# SDC_project.net
KiCad netlist of a schematic drawn in EAGLE
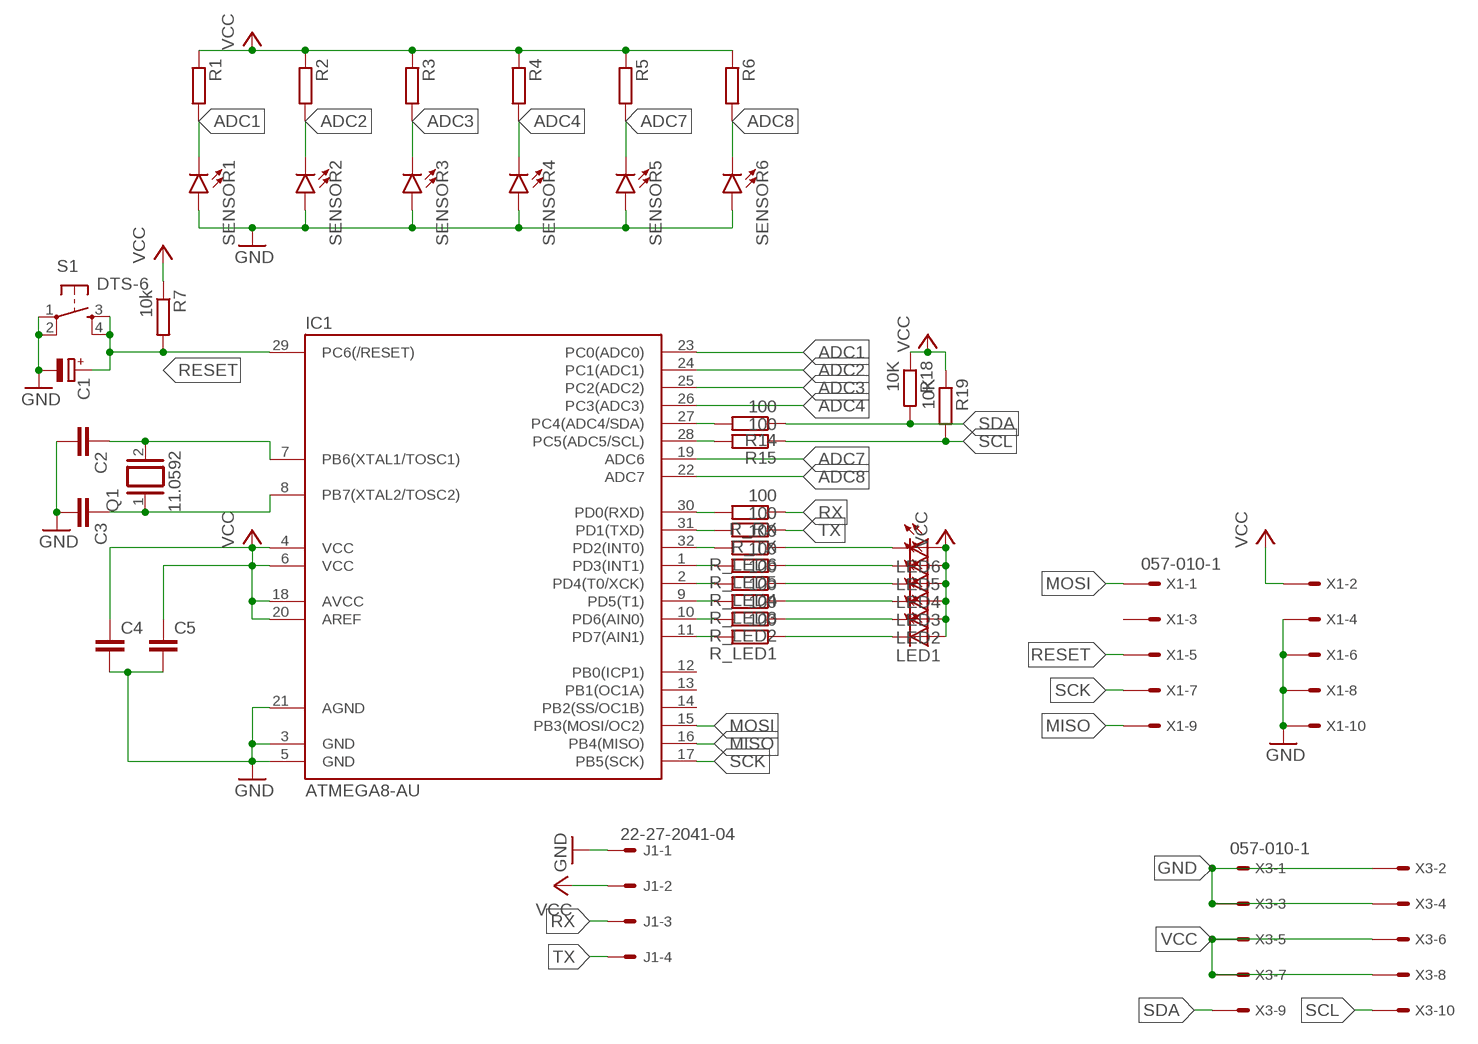
[diagram p0: schematic, sheet 1]

(export (version "E")
  (design (tool "Eeschema 10.0.6"))
  (components
    (comp (ref "C1")
      (value "CPOL-EUE2.5-5")
      (footprint "eagle-import:E2,5-5")
      (libsource (lib "eagle-import") (part "CPOL-EUE2.5-5"))
    )
    (comp (ref "C2")
      (value "C5/2.5")
      (footprint "eagle-import:C5B2.5")
      (libsource (lib "eagle-import") (part "C5/2.5"))
    )
    (comp (ref "C3")
      (value "C5/2.5")
      (footprint "eagle-import:C5B2.5")
      (libsource (lib "eagle-import") (part "C5/2.5"))
    )
    (comp (ref "C4")
      (value "C-EUC1206")
      (footprint "eagle-import:C1206")
      (libsource (lib "eagle-import") (part "C-EUC1206"))
    )
    (comp (ref "C5")
      (value "C-EUC1206")
      (footprint "eagle-import:C1206")
      (libsource (lib "eagle-import") (part "C-EUC1206"))
    )
    (comp (ref "IC1")
      (value "ATMEGA8-AU")
      (footprint "eagle-import:TQFP32-08")
      (libsource (lib "eagle-import") (part "ATMEGA8-AU"))
    )
    (comp (ref "J1")
      (value "22-27-2041-04")
      (footprint "eagle-import:6410-04")
      (fields (field (name "MF") "MOLEX"))
      (libsource (lib "eagle-import") (part "22-?-0427-2041"))
    )
    (comp (ref "LED1")
      (value "LEDSML0805")
      (footprint "eagle-import:SML0805")
      (libsource (lib "eagle-import") (part "LEDSML0805"))
    )
    (comp (ref "LED2")
      (value "LEDSML0805")
      (footprint "eagle-import:SML0805")
      (libsource (lib "eagle-import") (part "LEDSML0805"))
    )
    (comp (ref "LED3")
      (value "LEDSML0805")
      (footprint "eagle-import:SML0805")
      (libsource (lib "eagle-import") (part "LEDSML0805"))
    )
    (comp (ref "LED4")
      (value "LEDSML0805")
      (footprint "eagle-import:SML0805")
      (libsource (lib "eagle-import") (part "LEDSML0805"))
    )
    (comp (ref "LED5")
      (value "LEDSML0805")
      (footprint "eagle-import:SML0805")
      (libsource (lib "eagle-import") (part "LEDSML0805"))
    )
    (comp (ref "LED6")
      (value "LEDSML0805")
      (footprint "eagle-import:SML0805")
      (libsource (lib "eagle-import") (part "LEDSML0805"))
    )
    (comp (ref "Q1")
      (value "11.0592")
      (footprint "eagle-import:QS")
      (libsource (lib "eagle-import") (part "XTAL/S"))
    )
    (comp (ref "R1")
      (value "R-EU_R0805")
      (footprint "eagle-import:R0805")
      (libsource (lib "eagle-import") (part "R-EU_R0805"))
    )
    (comp (ref "R2")
      (value "R-EU_R0805")
      (footprint "eagle-import:R0805")
      (libsource (lib "eagle-import") (part "R-EU_R0805"))
    )
    (comp (ref "R3")
      (value "R-EU_R0805")
      (footprint "eagle-import:R0805")
      (libsource (lib "eagle-import") (part "R-EU_R0805"))
    )
    (comp (ref "R4")
      (value "R-EU_R0805")
      (footprint "eagle-import:R0805")
      (libsource (lib "eagle-import") (part "R-EU_R0805"))
    )
    (comp (ref "R5")
      (value "R-EU_R0805")
      (footprint "eagle-import:R0805")
      (libsource (lib "eagle-import") (part "R-EU_R0805"))
    )
    (comp (ref "R6")
      (value "R-EU_R0805")
      (footprint "eagle-import:R0805")
      (libsource (lib "eagle-import") (part "R-EU_R0805"))
    )
    (comp (ref "R7")
      (value "10k")
      (footprint "eagle-import:R0805")
      (libsource (lib "eagle-import") (part "R-EU_R0805"))
    )
    (comp (ref "R14")
      (value "100")
      (footprint "eagle-import:R0805")
      (libsource (lib "eagle-import") (part "R-EU_R0805"))
    )
    (comp (ref "R15")
      (value "100")
      (footprint "eagle-import:R0805")
      (libsource (lib "eagle-import") (part "R-EU_R0805"))
    )
    (comp (ref "R18")
      (value "10K")
      (footprint "eagle-import:R0805")
      (libsource (lib "eagle-import") (part "R-EU_R0805"))
    )
    (comp (ref "R19")
      (value "10K")
      (footprint "eagle-import:R0805")
      (libsource (lib "eagle-import") (part "R-EU_R0805"))
    )
    (comp (ref "R_LED1")
      (value "100")
      (footprint "eagle-import:R0805")
      (libsource (lib "eagle-import") (part "R-EU_R0805"))
    )
    (comp (ref "R_LED2")
      (value "100")
      (footprint "eagle-import:R0805")
      (libsource (lib "eagle-import") (part "R-EU_R0805"))
    )
    (comp (ref "R_LED3")
      (value "100")
      (footprint "eagle-import:R0805")
      (libsource (lib "eagle-import") (part "R-EU_R0805"))
    )
    (comp (ref "R_LED4")
      (value "100")
      (footprint "eagle-import:R0805")
      (libsource (lib "eagle-import") (part "R-EU_R0805"))
    )
    (comp (ref "R_LED5")
      (value "100")
      (footprint "eagle-import:R0805")
      (libsource (lib "eagle-import") (part "R-EU_R0805"))
    )
    (comp (ref "R_LED6")
      (value "100")
      (footprint "eagle-import:R0805")
      (libsource (lib "eagle-import") (part "R-EU_R0805"))
    )
    (comp (ref "R_RX")
      (value "100")
      (footprint "eagle-import:R0805")
      (libsource (lib "eagle-import") (part "R-EU_R0805"))
    )
    (comp (ref "R_TX")
      (value "100")
      (footprint "eagle-import:R0805")
      (libsource (lib "eagle-import") (part "R-EU_R0805"))
    )
    (comp (ref "S1")
      (value "DTS-6")
      (footprint "eagle-import:DTS-6")
      (libsource (lib "eagle-import") (part "DTS-6"))
    )
    (comp (ref "SENSOR1")
      (value "LED5MM")
      (footprint "eagle-import:LED_5MM")
      (libsource (lib "eagle-import") (part "LED5MM"))
    )
    (comp (ref "SENSOR2")
      (value "LED5MM")
      (footprint "eagle-import:LED_5MM")
      (libsource (lib "eagle-import") (part "LED5MM"))
    )
    (comp (ref "SENSOR3")
      (value "LED5MM")
      (footprint "eagle-import:LED_5MM")
      (libsource (lib "eagle-import") (part "LED5MM"))
    )
    (comp (ref "SENSOR4")
      (value "LED5MM")
      (footprint "eagle-import:LED_5MM")
      (libsource (lib "eagle-import") (part "LED5MM"))
    )
    (comp (ref "SENSOR5")
      (value "LED5MM")
      (footprint "eagle-import:LED_5MM")
      (libsource (lib "eagle-import") (part "LED5MM"))
    )
    (comp (ref "SENSOR6")
      (value "LED5MM")
      (footprint "eagle-import:LED_5MM")
      (libsource (lib "eagle-import") (part "LED5MM"))
    )
    (comp (ref "X1")
      (value "057-010-1")
      (footprint "eagle-import:057-010-1")
      (libsource (lib "eagle-import") (part "057-010-1"))
    )
    (comp (ref "X3")
      (value "057-010-1")
      (footprint "eagle-import:057-010-1")
      (libsource (lib "eagle-import") (part "057-010-1"))
    )
  )
  (nets
    (net (code "1") (name "ADC1") (class "Default")
      (node (ref "IC1") (pin "23") (pinfunction "PC0(ADC0)_23") (pintype "bidirectional"))
      (node (ref "R1") (pin "2") (pinfunction "2_2") (pintype "passive"))
      (node (ref "SENSOR1") (pin "K") (pinfunction "C_K") (pintype "passive"))
    )
    (net (code "2") (name "ADC2") (class "Default")
      (node (ref "IC1") (pin "24") (pinfunction "PC1(ADC1)_24") (pintype "bidirectional"))
      (node (ref "R2") (pin "2") (pinfunction "2_2") (pintype "passive"))
      (node (ref "SENSOR2") (pin "K") (pinfunction "C_K") (pintype "passive"))
    )
    (net (code "3") (name "ADC3") (class "Default")
      (node (ref "IC1") (pin "25") (pinfunction "PC2(ADC2)_25") (pintype "bidirectional"))
      (node (ref "R3") (pin "2") (pinfunction "2_2") (pintype "passive"))
      (node (ref "SENSOR3") (pin "K") (pinfunction "C_K") (pintype "passive"))
    )
    (net (code "4") (name "ADC4") (class "Default")
      (node (ref "IC1") (pin "26") (pinfunction "PC3(ADC3)_26") (pintype "bidirectional"))
      (node (ref "R4") (pin "2") (pinfunction "2_2") (pintype "passive"))
      (node (ref "SENSOR4") (pin "K") (pinfunction "C_K") (pintype "passive"))
    )
    (net (code "5") (name "ADC7") (class "Default")
      (node (ref "IC1") (pin "19") (pinfunction "ADC6_19") (pintype "passive"))
      (node (ref "R5") (pin "2") (pinfunction "2_2") (pintype "passive"))
      (node (ref "SENSOR5") (pin "K") (pinfunction "C_K") (pintype "passive"))
    )
    (net (code "6") (name "ADC8") (class "Default")
      (node (ref "IC1") (pin "22") (pinfunction "ADC7_22") (pintype "passive"))
      (node (ref "R6") (pin "2") (pinfunction "2_2") (pintype "passive"))
      (node (ref "SENSOR6") (pin "K") (pinfunction "C_K") (pintype "passive"))
    )
    (net (code "7") (name "GND") (class "Default")
      (node (ref "C1") (pin "-") (pinfunction "-_-") (pintype "passive"))
      (node (ref "C2") (pin "2") (pinfunction "2_2") (pintype "passive"))
      (node (ref "C3") (pin "2") (pinfunction "2_2") (pintype "passive"))
      (node (ref "C4") (pin "2") (pinfunction "2_2") (pintype "passive"))
      (node (ref "C5") (pin "2") (pinfunction "2_2") (pintype "passive"))
      (node (ref "IC1") (pin "21") (pinfunction "AGND_21") (pintype "power_in"))
      (node (ref "IC1") (pin "3") (pinfunction "GND_3") (pintype "power_in"))
      (node (ref "IC1") (pin "5") (pinfunction "GND_5") (pintype "power_in"))
      (node (ref "J1") (pin "1") (pinfunction "S_1") (pintype "passive"))
      (node (ref "S1") (pin "1") (pinfunction "1_1") (pintype "passive"))
      (node (ref "S1") (pin "2") (pinfunction "2_2") (pintype "passive"))
      (node (ref "SENSOR1") (pin "A") (pinfunction "A_A") (pintype "passive"))
      (node (ref "SENSOR2") (pin "A") (pinfunction "A_A") (pintype "passive"))
      (node (ref "SENSOR3") (pin "A") (pinfunction "A_A") (pintype "passive"))
      (node (ref "SENSOR4") (pin "A") (pinfunction "A_A") (pintype "passive"))
      (node (ref "SENSOR5") (pin "A") (pinfunction "A_A") (pintype "passive"))
      (node (ref "SENSOR6") (pin "A") (pinfunction "A_A") (pintype "passive"))
      (node (ref "X1") (pin "10") (pinfunction "S_10") (pintype "passive"))
      (node (ref "X1") (pin "4") (pinfunction "S_4") (pintype "passive"))
      (node (ref "X1") (pin "6") (pinfunction "S_6") (pintype "passive"))
      (node (ref "X1") (pin "8") (pinfunction "S_8") (pintype "passive"))
      (node (ref "X3") (pin "1") (pinfunction "S_1") (pintype "passive"))
      (node (ref "X3") (pin "2") (pinfunction "S_2") (pintype "passive"))
      (node (ref "X3") (pin "3") (pinfunction "S_3") (pintype "passive"))
      (node (ref "X3") (pin "4") (pinfunction "S_4") (pintype "passive"))
    )
    (net (code "8") (name "MISO") (class "Default")
      (node (ref "IC1") (pin "16") (pinfunction "PB4(MISO)_16") (pintype "bidirectional"))
      (node (ref "X1") (pin "9") (pinfunction "S_9") (pintype "passive"))
    )
    (net (code "9") (name "MOSI") (class "Default")
      (node (ref "IC1") (pin "15") (pinfunction "PB3(MOSI/OC2)_15") (pintype "bidirectional"))
      (node (ref "X1") (pin "1") (pinfunction "S_1") (pintype "passive"))
    )
    (net (code "10") (name "Net-(IC1-PB6(XTAL1{slash}TOSC1))") (class "Default")
      (node (ref "C2") (pin "1") (pinfunction "1_1") (pintype "passive"))
      (node (ref "IC1") (pin "7") (pinfunction "PB6(XTAL1/TOSC1)_7") (pintype "bidirectional"))
      (node (ref "Q1") (pin "2") (pinfunction "2_2") (pintype "passive"))
    )
    (net (code "11") (name "Net-(IC1-PB7(XTAL2{slash}TOSC2))") (class "Default")
      (node (ref "C3") (pin "1") (pinfunction "1_1") (pintype "passive"))
      (node (ref "IC1") (pin "8") (pinfunction "PB7(XTAL2/TOSC2)_8") (pintype "bidirectional"))
      (node (ref "Q1") (pin "1") (pinfunction "1_1") (pintype "passive"))
    )
    (net (code "12") (name "Net-(IC1-PC4(ADC4{slash}SDA))") (class "Default")
      (node (ref "IC1") (pin "27") (pinfunction "PC4(ADC4/SDA)_27") (pintype "bidirectional"))
      (node (ref "R14") (pin "2") (pinfunction "2_2") (pintype "passive"))
    )
    (net (code "13") (name "Net-(IC1-PC5(ADC5{slash}SCL))") (class "Default")
      (node (ref "IC1") (pin "28") (pinfunction "PC5(ADC5/SCL)_28") (pintype "bidirectional"))
      (node (ref "R15") (pin "2") (pinfunction "2_2") (pintype "passive"))
    )
    (net (code "14") (name "Net-(IC1-PD0(RXD))") (class "Default")
      (node (ref "IC1") (pin "30") (pinfunction "PD0(RXD)_30") (pintype "bidirectional"))
      (node (ref "R_RX") (pin "2") (pinfunction "2_2") (pintype "passive"))
    )
    (net (code "15") (name "Net-(IC1-PD1(TXD))") (class "Default")
      (node (ref "IC1") (pin "31") (pinfunction "PD1(TXD)_31") (pintype "bidirectional"))
      (node (ref "R_TX") (pin "2") (pinfunction "2_2") (pintype "passive"))
    )
    (net (code "16") (name "Net-(IC1-PD2(INT0))") (class "Default")
      (node (ref "IC1") (pin "32") (pinfunction "PD2(INT0)_32") (pintype "bidirectional"))
      (node (ref "R_LED6") (pin "2") (pinfunction "2_2") (pintype "passive"))
    )
    (net (code "17") (name "Net-(IC1-PD3(INT1))") (class "Default")
      (node (ref "IC1") (pin "1") (pinfunction "PD3(INT1)_1") (pintype "bidirectional"))
      (node (ref "R_LED5") (pin "2") (pinfunction "2_2") (pintype "passive"))
    )
    (net (code "18") (name "Net-(IC1-PD4(T0{slash}XCK))") (class "Default")
      (node (ref "IC1") (pin "2") (pinfunction "PD4(T0/XCK)_2") (pintype "bidirectional"))
      (node (ref "R_LED4") (pin "2") (pinfunction "2_2") (pintype "passive"))
    )
    (net (code "19") (name "Net-(IC1-PD5(T1))") (class "Default")
      (node (ref "IC1") (pin "9") (pinfunction "PD5(T1)_9") (pintype "bidirectional"))
      (node (ref "R_LED3") (pin "2") (pinfunction "2_2") (pintype "passive"))
    )
    (net (code "20") (name "Net-(IC1-PD6(AIN0))") (class "Default")
      (node (ref "IC1") (pin "10") (pinfunction "PD6(AIN0)_10") (pintype "bidirectional"))
      (node (ref "R_LED2") (pin "2") (pinfunction "2_2") (pintype "passive"))
    )
    (net (code "21") (name "Net-(IC1-PD7(AIN1))") (class "Default")
      (node (ref "IC1") (pin "11") (pinfunction "PD7(AIN1)_11") (pintype "bidirectional"))
      (node (ref "R_LED1") (pin "2") (pinfunction "2_2") (pintype "passive"))
    )
    (net (code "22") (name "Net-(LED1-PadC)") (class "Default")
      (node (ref "LED1") (pin "C") (pinfunction "C_C") (pintype "passive"))
      (node (ref "R_LED1") (pin "1") (pinfunction "1_1") (pintype "passive"))
    )
    (net (code "23") (name "Net-(LED2-PadC)") (class "Default")
      (node (ref "LED2") (pin "C") (pinfunction "C_C") (pintype "passive"))
      (node (ref "R_LED2") (pin "1") (pinfunction "1_1") (pintype "passive"))
    )
    (net (code "24") (name "Net-(LED3-PadC)") (class "Default")
      (node (ref "LED3") (pin "C") (pinfunction "C_C") (pintype "passive"))
      (node (ref "R_LED3") (pin "1") (pinfunction "1_1") (pintype "passive"))
    )
    (net (code "25") (name "Net-(LED4-PadC)") (class "Default")
      (node (ref "LED4") (pin "C") (pinfunction "C_C") (pintype "passive"))
      (node (ref "R_LED4") (pin "1") (pinfunction "1_1") (pintype "passive"))
    )
    (net (code "26") (name "Net-(LED5-PadC)") (class "Default")
      (node (ref "LED5") (pin "C") (pinfunction "C_C") (pintype "passive"))
      (node (ref "R_LED5") (pin "1") (pinfunction "1_1") (pintype "passive"))
    )
    (net (code "27") (name "Net-(LED6-PadC)") (class "Default")
      (node (ref "LED6") (pin "C") (pinfunction "C_C") (pintype "passive"))
      (node (ref "R_LED6") (pin "1") (pinfunction "1_1") (pintype "passive"))
    )
    (net (code "28") (name "RESET") (class "Default")
      (node (ref "C1") (pin "+") (pinfunction "+_+") (pintype "passive"))
      (node (ref "IC1") (pin "29") (pinfunction "PC6(/RESET)_29") (pintype "bidirectional"))
      (node (ref "R7") (pin "2") (pinfunction "2_2") (pintype "passive"))
      (node (ref "S1") (pin "3") (pinfunction "3_3") (pintype "passive"))
      (node (ref "S1") (pin "4") (pinfunction "4_4") (pintype "passive"))
      (node (ref "X1") (pin "5") (pinfunction "S_5") (pintype "passive"))
    )
    (net (code "29") (name "RX") (class "Default")
      (node (ref "J1") (pin "3") (pinfunction "S_3") (pintype "passive"))
      (node (ref "R_RX") (pin "1") (pinfunction "1_1") (pintype "passive"))
    )
    (net (code "30") (name "SCK") (class "Default")
      (node (ref "IC1") (pin "17") (pinfunction "PB5(SCK)_17") (pintype "bidirectional"))
      (node (ref "X1") (pin "7") (pinfunction "S_7") (pintype "passive"))
    )
    (net (code "31") (name "SCL") (class "Default")
      (node (ref "R15") (pin "1") (pinfunction "1_1") (pintype "passive"))
      (node (ref "R19") (pin "2") (pinfunction "2_2") (pintype "passive"))
      (node (ref "X3") (pin "10") (pinfunction "S_10") (pintype "passive"))
    )
    (net (code "32") (name "SDA") (class "Default")
      (node (ref "R14") (pin "1") (pinfunction "1_1") (pintype "passive"))
      (node (ref "R18") (pin "2") (pinfunction "2_2") (pintype "passive"))
      (node (ref "X3") (pin "9") (pinfunction "S_9") (pintype "passive"))
    )
    (net (code "33") (name "TX") (class "Default")
      (node (ref "J1") (pin "4") (pinfunction "S_4") (pintype "passive"))
      (node (ref "R_TX") (pin "1") (pinfunction "1_1") (pintype "passive"))
    )
    (net (code "34") (name "VCC") (class "Default")
      (node (ref "C4") (pin "1") (pinfunction "1_1") (pintype "passive"))
      (node (ref "C5") (pin "1") (pinfunction "1_1") (pintype "passive"))
      (node (ref "IC1") (pin "18") (pinfunction "AVCC_18") (pintype "passive"))
      (node (ref "IC1") (pin "20") (pinfunction "AREF_20") (pintype "passive"))
      (node (ref "IC1") (pin "4") (pinfunction "VCC_4") (pintype "power_in"))
      (node (ref "IC1") (pin "6") (pinfunction "VCC_6") (pintype "power_in"))
      (node (ref "J1") (pin "2") (pinfunction "S_2") (pintype "passive"))
      (node (ref "LED1") (pin "A") (pinfunction "A_A") (pintype "passive"))
      (node (ref "LED2") (pin "A") (pinfunction "A_A") (pintype "passive"))
      (node (ref "LED3") (pin "A") (pinfunction "A_A") (pintype "passive"))
      (node (ref "LED4") (pin "A") (pinfunction "A_A") (pintype "passive"))
      (node (ref "LED5") (pin "A") (pinfunction "A_A") (pintype "passive"))
      (node (ref "LED6") (pin "A") (pinfunction "A_A") (pintype "passive"))
      (node (ref "R1") (pin "1") (pinfunction "1_1") (pintype "passive"))
      (node (ref "R18") (pin "1") (pinfunction "1_1") (pintype "passive"))
      (node (ref "R19") (pin "1") (pinfunction "1_1") (pintype "passive"))
      (node (ref "R2") (pin "1") (pinfunction "1_1") (pintype "passive"))
      (node (ref "R3") (pin "1") (pinfunction "1_1") (pintype "passive"))
      (node (ref "R4") (pin "1") (pinfunction "1_1") (pintype "passive"))
      (node (ref "R5") (pin "1") (pinfunction "1_1") (pintype "passive"))
      (node (ref "R6") (pin "1") (pinfunction "1_1") (pintype "passive"))
      (node (ref "R7") (pin "1") (pinfunction "1_1") (pintype "passive"))
      (node (ref "X1") (pin "2") (pinfunction "S_2") (pintype "passive"))
      (node (ref "X3") (pin "5") (pinfunction "S_5") (pintype "passive"))
      (node (ref "X3") (pin "6") (pinfunction "S_6") (pintype "passive"))
      (node (ref "X3") (pin "7") (pinfunction "S_7") (pintype "passive"))
      (node (ref "X3") (pin "8") (pinfunction "S_8") (pintype "passive"))
    )
    (net (code "35") (name "unconnected-(IC1-PB0(ICP1)-Pad12)") (class "Default")
      (node (ref "IC1") (pin "12") (pinfunction "PB0(ICP1)_12") (pintype "bidirectional"))
    )
    (net (code "36") (name "unconnected-(IC1-PB1(OC1A)-Pad13)") (class "Default")
      (node (ref "IC1") (pin "13") (pinfunction "PB1(OC1A)_13") (pintype "bidirectional"))
    )
    (net (code "37") (name "unconnected-(IC1-PB2(SS{slash}OC1B)-Pad14)") (class "Default")
      (node (ref "IC1") (pin "14") (pinfunction "PB2(SS/OC1B)_14") (pintype "bidirectional"))
    )
    (net (code "38") (name "unconnected-(X1D-S-Pad3)") (class "Default")
      (node (ref "X1") (pin "3") (pinfunction "S_3") (pintype "passive"))
    )
  )
)
